# HGS_Reflector.net
KiCad netlist of a schematic drawn in EAGLE
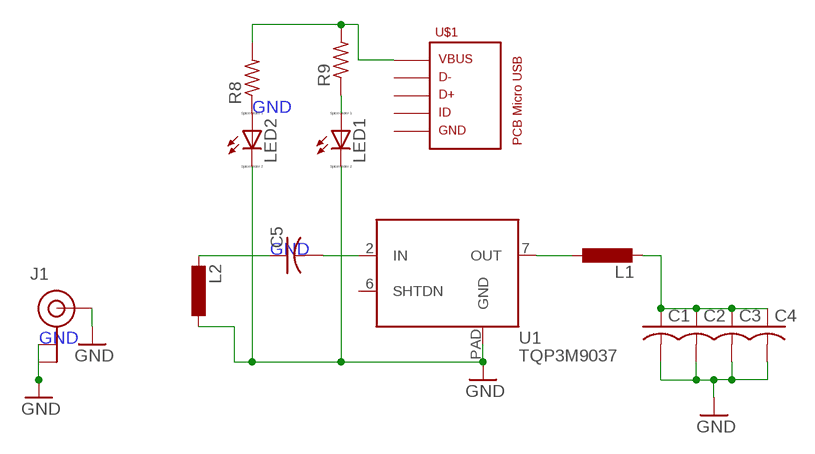
[diagram p0: schematic, sheet 1]

(export (version "E")
  (design (tool "Eeschema 10.0.6"))
  (components
    (comp (ref "C1")
      (value "C-USC1210")
      (footprint "eagle-import:C1210")
      (libsource (lib "eagle-import") (part "C-USC1210"))
    )
    (comp (ref "C2")
      (value "C-USC1210")
      (footprint "eagle-import:C1210")
      (libsource (lib "eagle-import") (part "C-USC1210"))
    )
    (comp (ref "C3")
      (value "C-USC1210")
      (footprint "eagle-import:C1210")
      (libsource (lib "eagle-import") (part "C-USC1210"))
    )
    (comp (ref "C4")
      (value "C-USC1210")
      (footprint "eagle-import:C1210")
      (libsource (lib "eagle-import") (part "C-USC1210"))
    )
    (comp (ref "C5")
      (value "C-USC1210")
      (footprint "eagle-import:C1210")
      (libsource (lib "eagle-import") (part "C-USC1210"))
    )
    (comp (ref "J1")
      (value "U.FL")
      (footprint "eagle-import:U.FL")
      (libsource (lib "eagle-import") (part "U.FL"))
    )
    (comp (ref "L1")
      (value "L-EUL3216C")
      (footprint "eagle-import:L3216C")
      (libsource (lib "eagle-import") (part "L-EUL3216C"))
    )
    (comp (ref "L2")
      (value "L-EUL3216C")
      (footprint "eagle-import:L3216C")
      (libsource (lib "eagle-import") (part "L-EUL3216C"))
    )
    (comp (ref "LED1")
      (value "LED_E")
      (footprint "eagle-import:LED_1206")
      (libsource (lib "eagle-import") (part "LED_E"))
    )
    (comp (ref "LED2")
      (value "LED_E")
      (footprint "eagle-import:LED_1206")
      (libsource (lib "eagle-import") (part "LED_E"))
    )
    (comp (ref "R8")
      (value "R-US_R0402")
      (footprint "eagle-import:R0402")
      (libsource (lib "eagle-import") (part "R-US_R0402"))
    )
    (comp (ref "R9")
      (value "R-US_R0402")
      (footprint "eagle-import:R0402")
      (libsource (lib "eagle-import") (part "R-US_R0402"))
    )
    (comp (ref "U$1")
      (value "PCB_MICRO_USB_BSS_1")
      (footprint "eagle-import:USB_TYPE_B_SS_1")
      (libsource (lib "eagle-import") (part "PCB_MICRO_USB_BSS_1"))
    )
    (comp (ref "U1")
      (value "TQP3M9037")
      (footprint "eagle-import:DFN8-2X2-WITH-PAD")
      (libsource (lib "eagle-import") (part "TQP3M9037"))
    )
  )
  (nets
    (net (code "1") (name "GND") (class "Default")
      (node (ref "C1") (pin "2") (pinfunction "2_2") (pintype "passive"))
      (node (ref "C2") (pin "2") (pinfunction "2_2") (pintype "passive"))
      (node (ref "C3") (pin "2") (pinfunction "2_2") (pintype "passive"))
      (node (ref "C4") (pin "2") (pinfunction "2_2") (pintype "passive"))
      (node (ref "J1") (pin "1") (pinfunction "GND_1") (pintype "bidirectional"))
      (node (ref "J1") (pin "2") (pinfunction "GND_2") (pintype "bidirectional"))
      (node (ref "J1") (pin "FEED") (pinfunction "SIGNAL_FEED") (pintype "bidirectional"))
      (node (ref "L2") (pin "1") (pinfunction "1_1") (pintype "passive"))
      (node (ref "LED1") (pin "C") (pinfunction "C_C") (pintype "passive"))
      (node (ref "LED2") (pin "C") (pinfunction "C_C") (pintype "passive"))
      (node (ref "U1") (pin "PAD") (pinfunction "GND_PAD") (pintype "power_in"))
    )
    (net (code "2") (name "Net-(C1-Pad1)") (class "Default")
      (node (ref "C1") (pin "1") (pinfunction "1_1") (pintype "passive"))
      (node (ref "C2") (pin "1") (pinfunction "1_1") (pintype "passive"))
      (node (ref "C3") (pin "1") (pinfunction "1_1") (pintype "passive"))
      (node (ref "C4") (pin "1") (pinfunction "1_1") (pintype "passive"))
      (node (ref "L1") (pin "2") (pinfunction "2_2") (pintype "passive"))
    )
    (net (code "3") (name "Net-(C5-Pad1)") (class "Default")
      (node (ref "C5") (pin "1") (pinfunction "1_1") (pintype "passive"))
      (node (ref "L2") (pin "2") (pinfunction "2_2") (pintype "passive"))
    )
    (net (code "4") (name "Net-(LED1-PadA)") (class "Default")
      (node (ref "LED1") (pin "A") (pinfunction "A_A") (pintype "passive"))
      (node (ref "R9") (pin "1") (pinfunction "1_1") (pintype "passive"))
    )
    (net (code "5") (name "Net-(LED2-PadA)") (class "Default")
      (node (ref "LED2") (pin "A") (pinfunction "A_A") (pintype "passive"))
      (node (ref "R8") (pin "1") (pinfunction "1_1") (pintype "passive"))
    )
    (net (code "6") (name "Net-(R8-Pad2)") (class "Default")
      (node (ref "R8") (pin "2") (pinfunction "2_2") (pintype "passive"))
      (node (ref "R9") (pin "2") (pinfunction "2_2") (pintype "passive"))
      (node (ref "U$1") (pin "1") (pinfunction "1_1") (pintype "bidirectional"))
    )
    (net (code "7") (name "Net-(U1-IN)") (class "Default")
      (node (ref "C5") (pin "2") (pinfunction "2_2") (pintype "passive"))
      (node (ref "U1") (pin "2") (pinfunction "IN_2") (pintype "input"))
    )
    (net (code "8") (name "Net-(U1-OUT)") (class "Default")
      (node (ref "L1") (pin "1") (pinfunction "1_1") (pintype "passive"))
      (node (ref "U1") (pin "7") (pinfunction "OUT_7") (pintype "output"))
    )
    (net (code "9") (name "unconnected-(U$1-Pad2)") (class "Default")
      (node (ref "U$1") (pin "2") (pinfunction "2_2") (pintype "bidirectional"))
    )
    (net (code "10") (name "unconnected-(U$1-Pad3)") (class "Default")
      (node (ref "U$1") (pin "3") (pinfunction "3_3") (pintype "bidirectional"))
    )
    (net (code "11") (name "unconnected-(U$1-Pad4)") (class "Default")
      (node (ref "U$1") (pin "4") (pinfunction "4_4") (pintype "bidirectional"))
    )
    (net (code "12") (name "unconnected-(U$1-Pad5)") (class "Default")
      (node (ref "U$1") (pin "5") (pinfunction "5_5") (pintype "bidirectional"))
    )
    (net (code "13") (name "unconnected-(U1-SHTDN-Pad6)") (class "Default")
      (node (ref "U1") (pin "6") (pinfunction "SHTDN_6") (pintype "input"))
    )
  )
)
